# NO2-CO2_Sensor.net
KiCad netlist of a schematic drawn in Altium Designer
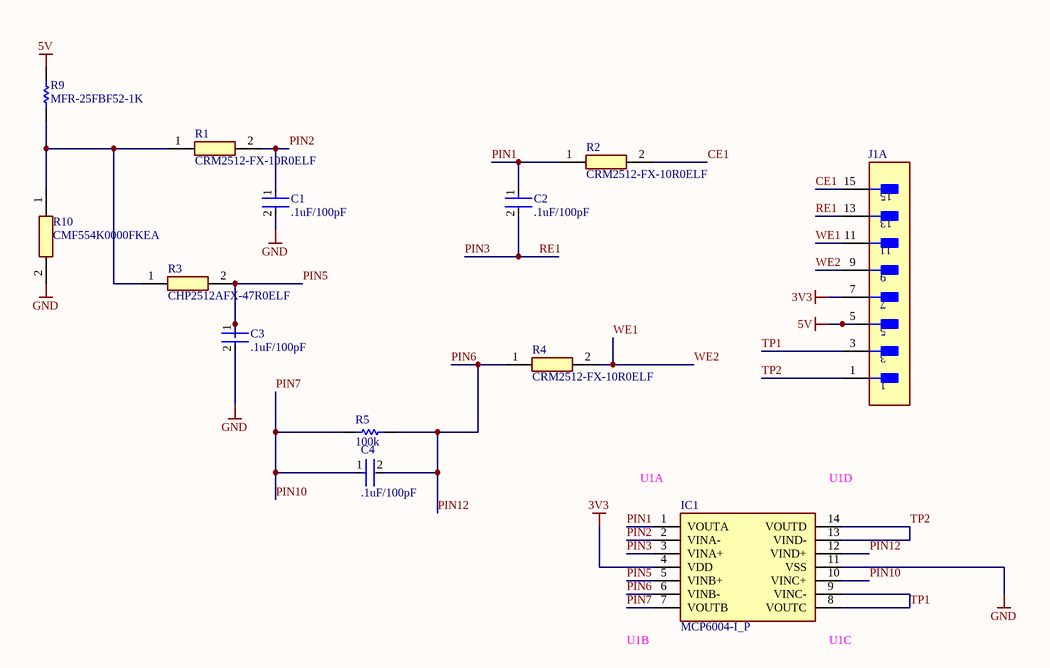
[diagram p0: NO2-CO2 Sensor.SchDoc]

(export (version "E")
  (design (tool "Eeschema 10.0.6"))
  (components
    (comp (ref "C1")
      (value ".1uF/100pF")
      (footprint "FP-RCE0DB-MFG")
      (description "Cap Ceramic 100pF 100V C0G ±5% Radial 2.5mm +125°C Ammo Pack")
      (fields (field (name "TOLERANCE") "5%"))
      (libsource (lib "Altium Content Vault") (part "b4654b650e69147ec39a6b967a45e02"))
    )
    (comp (ref "C2")
      (value ".1uF/100pF")
      (footprint "FP-RCE0DB-MFG")
      (description "Cap Ceramic 100pF 100V C0G ±5% Radial 2.5mm +125°C Ammo Pack")
      (fields (field (name "TOLERANCE") "5%"))
      (libsource (lib "Altium Content Vault") (part "b4654b650e69147ec39a6b967a45e02"))
    )
    (comp (ref "C3")
      (value ".1uF/100pF")
      (footprint "FP-RCE0DB-MFG")
      (description "Cap Ceramic 100pF 100V C0G ±5% Radial 2.5mm +125°C Ammo Pack")
      (fields (field (name "TOLERANCE") "5%"))
      (libsource (lib "Altium Content Vault") (part "b4654b650e69147ec39a6b967a45e02"))
    )
    (comp (ref "C4")
      (value ".1uF/100pF")
      (footprint "FP-RCE0DB-MFG")
      (description "Cap Ceramic 100pF 100V C0G ±5% Radial 2.5mm +125°C Ammo Pack")
      (fields (field (name "TOLERANCE") "5%"))
      (libsource (lib "Altium Content Vault") (part "b4654b650e69147ec39a6b967a45e02"))
    )
    (comp (ref "IC1")
      (value "MCP6004-I_P")
      (footprint "SamacSys:DIP794W56P254L1905H432Q14N")
      (description "Integrated Circuit")
      (fields
        (field (name "MANUFACTURER_PART_NUMBER") "MCP6004-I/P")
        (field (name "MOUSER PART NUMBER") "579-MCP6004-I/P")
      )
      (libsource (lib "*") (part "MCP6004-I_P"))
    )
    (comp (ref "J1")
      (value "~")
      (footprint "FP-87227-8-MFG")
      (description "CONN HEADER VERT 16POS 2.54MM")
      (fields
        (field (name "MANUFACTURER") "TE Connectivity")
        (field (name "MANUFACTURER PART NUMBER") "87227-8")
      )
      (libsource (lib "Altium Content Vault") (part "4b6d22b45e2f925f038cba5d936fbcc"))
    )
    (comp (ref "R1")
      (value "CRM2512-FX-10R0ELF")
      (footprint "SamacSys:RESC6331X80N")
      (description "Resistor")
      (fields (field (name "MOUSER PART NUMBER") "652-CRM2512FX10R0ELF"))
      (libsource (lib "*") (part "CRM2512-FX-10R0ELF"))
    )
    (comp (ref "R2")
      (value "CRM2512-FX-10R0ELF")
      (footprint "SamacSys:RESC6331X80N")
      (description "Resistor")
      (fields (field (name "MOUSER PART NUMBER") "652-CRM2512FX10R0ELF"))
      (libsource (lib "*") (part "CRM2512-FX-10R0ELF"))
    )
    (comp (ref "R3")
      (value "CHP2512AFX-47R0ELF")
      (footprint "SamacSys:RESC6431X130N")
      (description "Resistor")
      (fields (field (name "MOUSER PART NUMBER") "652-CHP2512AFX-47R0L"))
      (libsource (lib "*") (part "CHP2512AFX-47R0ELF"))
    )
    (comp (ref "R4")
      (value "CRM2512-FX-10R0ELF")
      (footprint "SamacSys:RESC6331X80N")
      (description "Resistor")
      (fields (field (name "MOUSER PART NUMBER") "652-CRM2512FX10R0ELF"))
      (libsource (lib "*") (part "CRM2512-FX-10R0ELF"))
    )
    (comp (ref "R5")
      (value "100k")
      (footprint "RESA60-630X240")
      (description "Axial Resistor, 100 KOhm, +/- 1%, 0.25 W, -55 to 155 degC, 2-Pin THD, RoHS, Bulk")
      (fields (field (name "TOLERANCE") "1%"))
      (libsource (lib "Altium Content Vault") (part "RES-2"))
    )
    (comp (ref "R9")
      (value "MFR-25FBF52-1K")
      (footprint "RESA60-630X240")
      (description "Axial Resistor, 1 KOhm, +/- 1%, 250 mW, -55 to 155 degC, 2-Pin THD, RoHS, Bulk")
      (fields (field (name "TOLERANCE") "1%"))
      (libsource (lib "Altium Content Vault") (part "RES-2"))
    )
    (comp (ref "R10")
      (value "CMF554K0000FKEA")
      (footprint "SamacSys:RESAD1526W69L610D229")
      (description "Resistor")
      (fields (field (name "MOUSER PART NUMBER") "71-CMF554K0000FKEA"))
      (libsource (lib "*") (part "CMF554K0000FKEA"))
    )
  )
  (nets
    (net (code "1") (name "/CE1") (class "Default")
      (node (ref "J1") (pin "15") (pinfunction "15_15") (pintype "passive"))
      (node (ref "R2") (pin "2") (pinfunction "2_2") (pintype "passive"))
    )
    (net (code "2") (name "/PIN1") (class "Default")
      (node (ref "C2") (pin "1") (pinfunction "1_1") (pintype "passive"))
      (node (ref "IC1") (pin "1") (pinfunction "VOUTA_1") (pintype "passive"))
      (node (ref "R2") (pin "1") (pinfunction "1_1") (pintype "passive"))
    )
    (net (code "3") (name "/PIN2") (class "Default")
      (node (ref "C1") (pin "1") (pinfunction "1_1") (pintype "passive"))
      (node (ref "IC1") (pin "2") (pinfunction "VINA-_2") (pintype "passive"))
      (node (ref "R1") (pin "2") (pinfunction "2_2") (pintype "passive"))
    )
    (net (code "4") (name "/PIN3") (class "Default")
      (node (ref "C2") (pin "2") (pinfunction "2_2") (pintype "passive"))
      (node (ref "IC1") (pin "3") (pinfunction "VINA+_3") (pintype "passive"))
      (node (ref "J1") (pin "13") (pinfunction "13_13") (pintype "passive"))
    )
    (net (code "5") (name "/PIN5") (class "Default")
      (node (ref "C3") (pin "1") (pinfunction "1_1") (pintype "passive"))
      (node (ref "IC1") (pin "5") (pinfunction "VINB+_5") (pintype "passive"))
      (node (ref "R3") (pin "2") (pinfunction "2_2") (pintype "passive"))
    )
    (net (code "6") (name "/PIN10") (class "Default")
      (node (ref "C4") (pin "1") (pinfunction "1_1") (pintype "passive"))
      (node (ref "IC1") (pin "10") (pinfunction "VINC+_10") (pintype "passive"))
      (node (ref "IC1") (pin "7") (pinfunction "VOUTB_7") (pintype "passive"))
      (node (ref "R5") (pin "1") (pinfunction "1_1") (pintype "passive"))
    )
    (net (code "7") (name "/PIN12") (class "Default")
      (node (ref "C4") (pin "2") (pinfunction "2_2") (pintype "passive"))
      (node (ref "IC1") (pin "12") (pinfunction "VIND+_12") (pintype "passive"))
      (node (ref "IC1") (pin "6") (pinfunction "VINB-_6") (pintype "passive"))
      (node (ref "R4") (pin "1") (pinfunction "1_1") (pintype "passive"))
      (node (ref "R5") (pin "2") (pinfunction "2_2") (pintype "passive"))
    )
    (net (code "8") (name "/TP1") (class "Default")
      (node (ref "IC1") (pin "8") (pinfunction "VOUTC_8") (pintype "passive"))
      (node (ref "IC1") (pin "9") (pinfunction "VINC-_9") (pintype "passive"))
      (node (ref "J1") (pin "3") (pinfunction "3_3") (pintype "passive"))
    )
    (net (code "9") (name "/TP2") (class "Default")
      (node (ref "IC1") (pin "13") (pinfunction "VIND-_13") (pintype "passive"))
      (node (ref "IC1") (pin "14") (pinfunction "VOUTD_14") (pintype "passive"))
      (node (ref "J1") (pin "1") (pinfunction "1_1") (pintype "passive"))
    )
    (net (code "10") (name "/WE1") (class "Default")
      (node (ref "J1") (pin "11") (pinfunction "11_11") (pintype "passive"))
      (node (ref "J1") (pin "9") (pinfunction "9_9") (pintype "passive"))
      (node (ref "R4") (pin "2") (pinfunction "2_2") (pintype "passive"))
    )
    (net (code "11") (name "3V3") (class "Default")
      (node (ref "IC1") (pin "4") (pinfunction "VDD_4") (pintype "passive"))
      (node (ref "J1") (pin "7") (pinfunction "7_7") (pintype "passive"))
    )
    (net (code "12") (name "5V") (class "Default")
      (node (ref "J1") (pin "5") (pinfunction "5_5") (pintype "passive"))
      (node (ref "R9") (pin "2") (pinfunction "2_2") (pintype "passive"))
    )
    (net (code "13") (name "GND") (class "Default")
      (node (ref "C1") (pin "2") (pinfunction "2_2") (pintype "passive"))
      (node (ref "C3") (pin "2") (pinfunction "2_2") (pintype "passive"))
      (node (ref "IC1") (pin "11") (pinfunction "VSS_11") (pintype "passive"))
      (node (ref "R10") (pin "2") (pinfunction "2_2") (pintype "passive"))
    )
    (net (code "14") (name "Net-(R1-Pad1)") (class "Default")
      (node (ref "R1") (pin "1") (pinfunction "1_1") (pintype "passive"))
      (node (ref "R10") (pin "1") (pinfunction "1_1") (pintype "passive"))
      (node (ref "R3") (pin "1") (pinfunction "1_1") (pintype "passive"))
      (node (ref "R9") (pin "1") (pinfunction "1_1") (pintype "passive"))
    )
  )
)
